# Diagrama_prima_rio.net
KiCad netlist of a schematic drawn in EAGLE
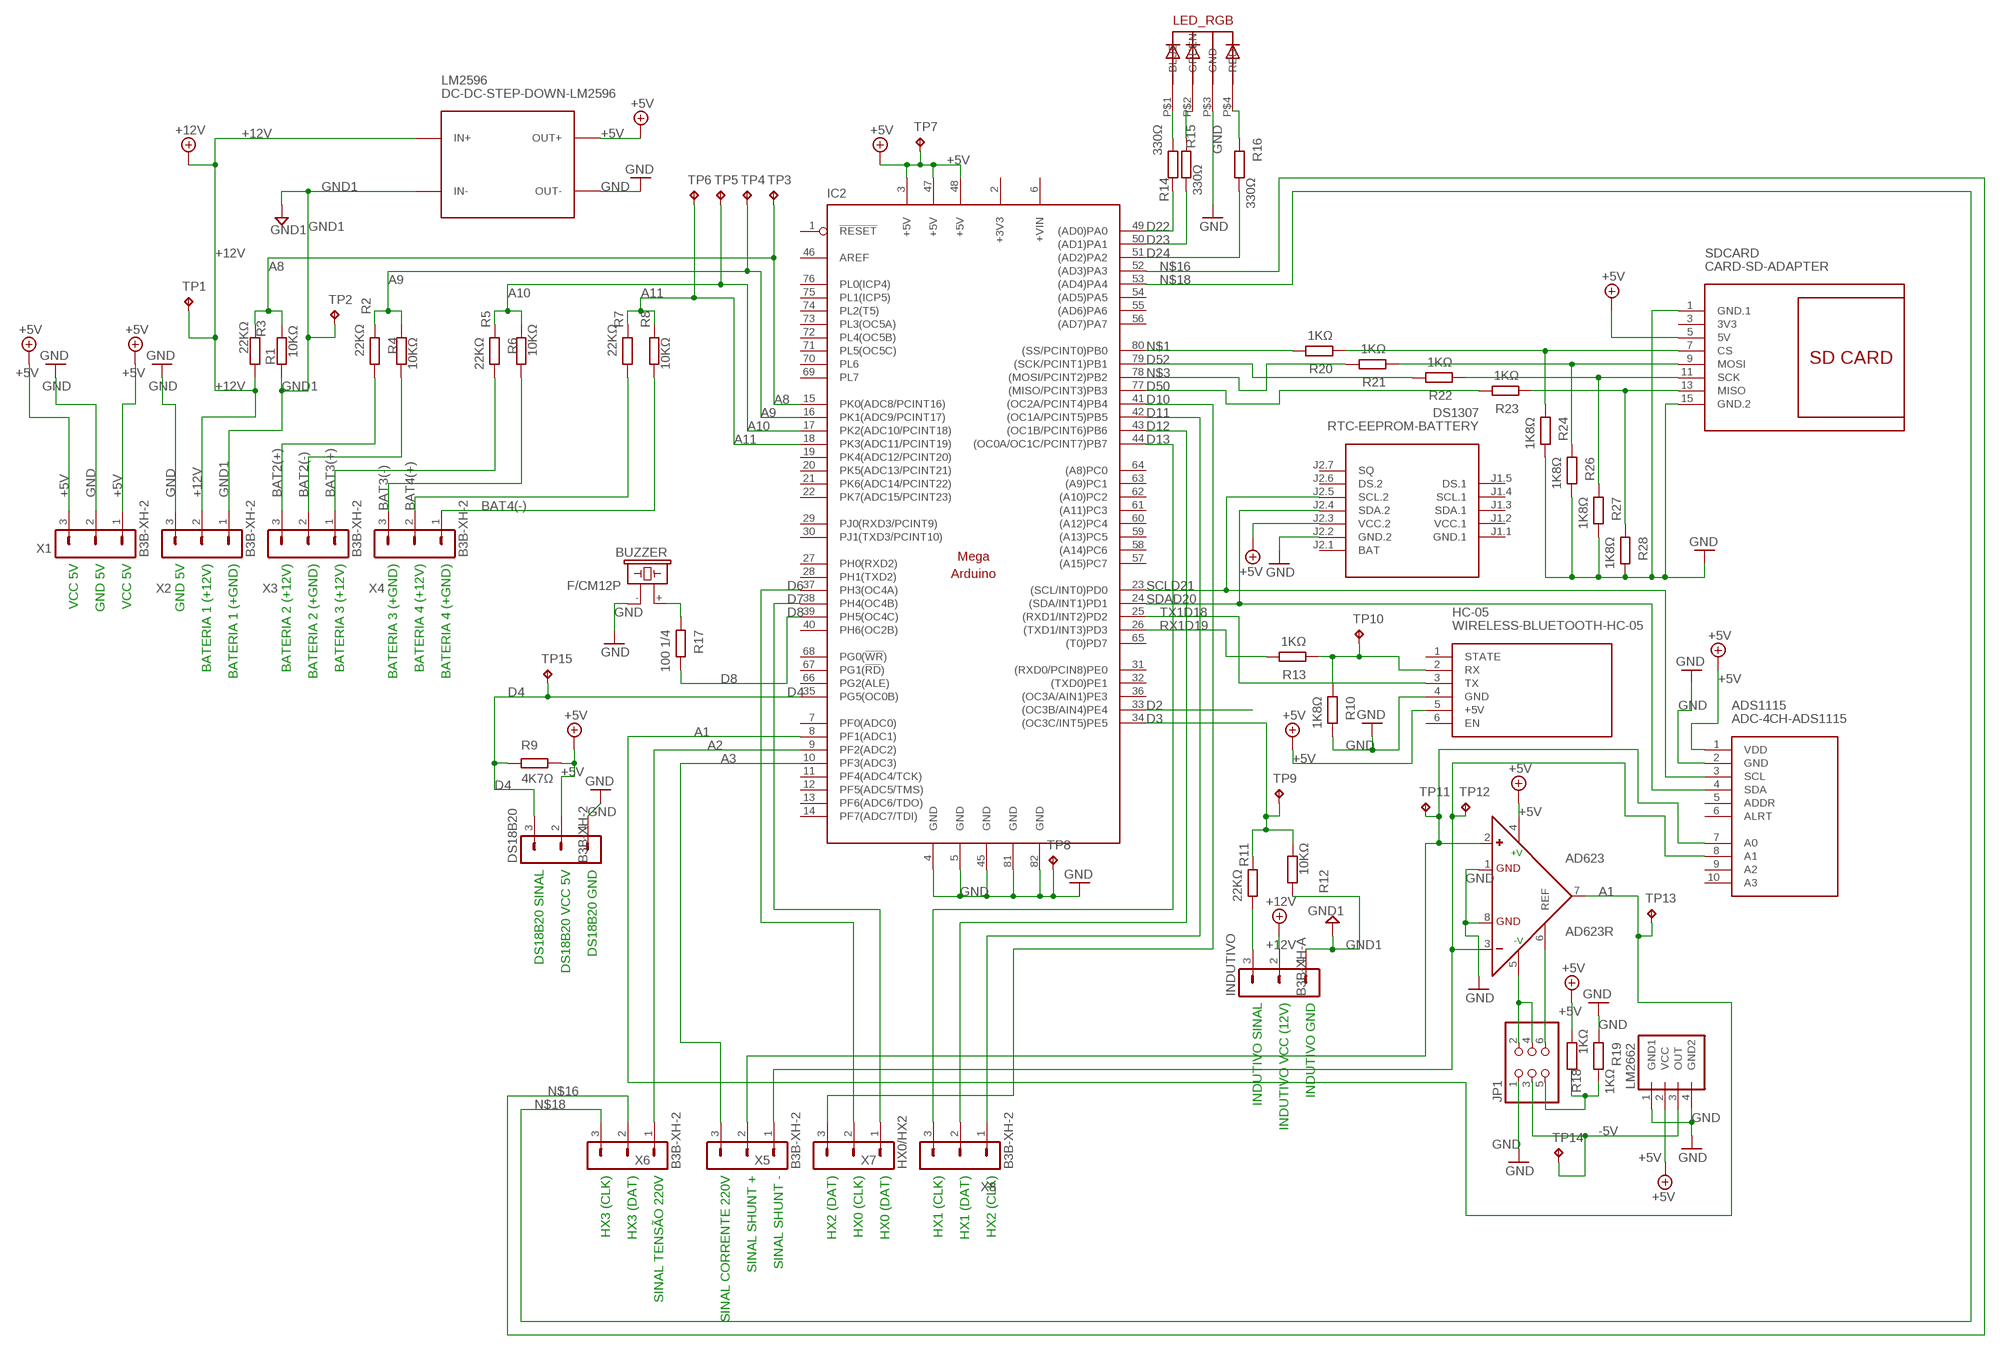
[diagram p0: schematic, sheet 1]

(export (version "E")
  (design (tool "Eeschema 10.0.6"))
  (components
    (comp (ref "AD623")
      (value "AD623R")
      (footprint "eagle-import:SO8")
      (fields (field (name "MPN") "AD623ARZ."))
      (libsource (lib "eagle-import") (part "AD623R"))
    )
    (comp (ref "ADS1115")
      (value "ADC-4CH-ADS1115")
      (footprint "eagle-import:ADC-4CH-ADS1115")
      (libsource (lib "eagle-import") (part "ADC-4CH-ADS1115"))
    )
    (comp (ref "BUZZER")
      (value "F/CM12P")
      (footprint "eagle-import:F_CM12P")
      (libsource (lib "eagle-import") (part "F/CM12P"))
    )
    (comp (ref "DS18B20")
      (value "B3B-XH-2")
      (footprint "eagle-import:B3B-XH-A")
      (libsource (lib "eagle-import") (part "B3B-XH-2"))
    )
    (comp (ref "DS1307")
      (value "RTC-EEPROM-BATTERY")
      (footprint "eagle-import:RTC-EEPROM-BATTERY")
      (libsource (lib "eagle-import") (part "RTC-EEPROM-BATTERY"))
    )
    (comp (ref "HC-05")
      (value "WIRELESS-BLUETOOTH-HC-05")
      (footprint "eagle-import:WIRELESS-BLUETOOTH-HC-05")
      (libsource (lib "eagle-import") (part "WIRELESS-BLUETOOTH-HC-05"))
    )
    (comp (ref "IC2")
      (value "MEGAARDUINO_11")
      (footprint "eagle-import:MEGA_ARDUINO_1")
      (libsource (lib "eagle-import") (part "MEGAARDUINO_11"))
    )
    (comp (ref "INDUTIVO")
      (value "B3B-XH-A")
      (footprint "eagle-import:B3B-XH-A")
      (libsource (lib "eagle-import") (part "con-JST XH_14082343_B3B-XH-A"))
    )
    (comp (ref "JP1")
      (value "PINHD-2X3")
      (footprint "eagle-import:2X03")
      (libsource (lib "eagle-import") (part "PINHD-2X3"))
    )
    (comp (ref "LED_RGB")
      (value "5MMRGBLED")
      (footprint "eagle-import:LED5MMRGB")
      (libsource (lib "eagle-import") (part "5MMRGBLED"))
    )
    (comp (ref "LM2596")
      (value "DC-DC-STEP-DOWN-LM2596")
      (footprint "eagle-import:DC-DC-STEP-DOWN-LM2596")
      (libsource (lib "eagle-import") (part "DC-DC-STEP-DOWN-LM2596"))
    )
    (comp (ref "LM2662")
      (value "LM2662")
      (footprint "eagle-import:LM2662")
      (libsource (lib "eagle-import") (part "LM2662"))
    )
    (comp (ref "R1")
      (value "10KΩ")
      (footprint "eagle-import:1_4W-0.41K")
      (libsource (lib "eagle-import") (part "1K1/4RESISTOR"))
    )
    (comp (ref "R2")
      (value "22KΩ")
      (footprint "eagle-import:1_4W-0.41K")
      (libsource (lib "eagle-import") (part "1K1/4RESISTOR"))
    )
    (comp (ref "R3")
      (value "22KΩ")
      (footprint "eagle-import:1_4W-0.41K")
      (libsource (lib "eagle-import") (part "1K1/4RESISTOR"))
    )
    (comp (ref "R4")
      (value "10KΩ")
      (footprint "eagle-import:1_4W-0.41K")
      (libsource (lib "eagle-import") (part "1K1/4RESISTOR"))
    )
    (comp (ref "R5")
      (value "22KΩ")
      (footprint "eagle-import:1_4W-0.41K")
      (libsource (lib "eagle-import") (part "1K1/4RESISTOR"))
    )
    (comp (ref "R6")
      (value "10KΩ")
      (footprint "eagle-import:1_4W-0.41K")
      (libsource (lib "eagle-import") (part "1K1/4RESISTOR"))
    )
    (comp (ref "R7")
      (value "22KΩ")
      (footprint "eagle-import:1_4W-0.41K")
      (libsource (lib "eagle-import") (part "1K1/4RESISTOR"))
    )
    (comp (ref "R8")
      (value "10KΩ")
      (footprint "eagle-import:1_4W-0.41K")
      (libsource (lib "eagle-import") (part "1K1/4RESISTOR"))
    )
    (comp (ref "R9")
      (value "4K7Ω")
      (footprint "eagle-import:1_4W-0.41K")
      (libsource (lib "eagle-import") (part "1K1/4RESISTOR"))
    )
    (comp (ref "R10")
      (value "1K8Ω")
      (footprint "eagle-import:1_4W-0.41K")
      (libsource (lib "eagle-import") (part "1K1/4RESISTOR"))
    )
    (comp (ref "R11")
      (value "22KΩ")
      (footprint "eagle-import:1_4W-0.41K")
      (libsource (lib "eagle-import") (part "1K1/4RESISTOR"))
    )
    (comp (ref "R12")
      (value "10KΩ")
      (footprint "eagle-import:1_4W-0.41K")
      (libsource (lib "eagle-import") (part "1K1/4RESISTOR"))
    )
    (comp (ref "R13")
      (value "1KΩ")
      (footprint "eagle-import:1_4W-0.41K")
      (libsource (lib "eagle-import") (part "1K1/4RESISTOR"))
    )
    (comp (ref "R14")
      (value "330Ω")
      (footprint "eagle-import:1_4W-0.41K")
      (libsource (lib "eagle-import") (part "1K1/4RESISTOR"))
    )
    (comp (ref "R15")
      (value "330Ω")
      (footprint "eagle-import:1_4W-0.41K")
      (libsource (lib "eagle-import") (part "1K1/4RESISTOR"))
    )
    (comp (ref "R16")
      (value "330Ω")
      (footprint "eagle-import:1_4W-0.41K")
      (libsource (lib "eagle-import") (part "1K1/4RESISTOR"))
    )
    (comp (ref "R17")
      (value "100 1/4")
      (footprint "eagle-import:1_4W-0.41K")
      (libsource (lib "eagle-import") (part "1K1/4RESISTOR"))
    )
    (comp (ref "R18")
      (value "1KΩ")
      (footprint "eagle-import:1_4W-0.41K")
      (libsource (lib "eagle-import") (part "1K1/4RESISTOR"))
    )
    (comp (ref "R19")
      (value "1KΩ")
      (footprint "eagle-import:1_4W-0.41K")
      (libsource (lib "eagle-import") (part "1K1/4RESISTOR"))
    )
    (comp (ref "R20")
      (value "1KΩ")
      (footprint "eagle-import:1_4W-0.41K")
      (libsource (lib "eagle-import") (part "1K1/4RESISTOR"))
    )
    (comp (ref "R21")
      (value "1KΩ")
      (footprint "eagle-import:1_4W-0.41K")
      (libsource (lib "eagle-import") (part "1K1/4RESISTOR"))
    )
    (comp (ref "R22")
      (value "1KΩ")
      (footprint "eagle-import:1_4W-0.41K")
      (libsource (lib "eagle-import") (part "1K1/4RESISTOR"))
    )
    (comp (ref "R23")
      (value "1KΩ")
      (footprint "eagle-import:1_4W-0.41K")
      (libsource (lib "eagle-import") (part "1K1/4RESISTOR"))
    )
    (comp (ref "R24")
      (value "1K8Ω")
      (footprint "eagle-import:1_4W-0.41K")
      (libsource (lib "eagle-import") (part "1K1/4RESISTOR"))
    )
    (comp (ref "R26")
      (value "1K8Ω")
      (footprint "eagle-import:1_4W-0.41K")
      (libsource (lib "eagle-import") (part "1K1/4RESISTOR"))
    )
    (comp (ref "R27")
      (value "1K8Ω")
      (footprint "eagle-import:1_4W-0.41K")
      (libsource (lib "eagle-import") (part "1K1/4RESISTOR"))
    )
    (comp (ref "R28")
      (value "1K8Ω")
      (footprint "eagle-import:1_4W-0.41K")
      (libsource (lib "eagle-import") (part "1K1/4RESISTOR"))
    )
    (comp (ref "SDCARD")
      (value "CARD-SD-ADAPTER")
      (footprint "eagle-import:CARD-SD-ADAPTER")
      (libsource (lib "eagle-import") (part "CARD-SD-ADAPTER"))
    )
    (comp (ref "TP1")
      (value "TPB1,27")
      (footprint "eagle-import:B1,27")
      (libsource (lib "eagle-import") (part "TPB1,27"))
    )
    (comp (ref "TP2")
      (value "TPB1,27")
      (footprint "eagle-import:B1,27")
      (libsource (lib "eagle-import") (part "TPB1,27"))
    )
    (comp (ref "TP3")
      (value "TPB1,27")
      (footprint "eagle-import:B1,27")
      (libsource (lib "eagle-import") (part "TPB1,27"))
    )
    (comp (ref "TP4")
      (value "TPB1,27")
      (footprint "eagle-import:B1,27")
      (libsource (lib "eagle-import") (part "TPB1,27"))
    )
    (comp (ref "TP5")
      (value "TPB1,27")
      (footprint "eagle-import:B1,27")
      (libsource (lib "eagle-import") (part "TPB1,27"))
    )
    (comp (ref "TP6")
      (value "TPB1,27")
      (footprint "eagle-import:B1,27")
      (libsource (lib "eagle-import") (part "TPB1,27"))
    )
    (comp (ref "TP7")
      (value "TPB1,27")
      (footprint "eagle-import:B1,27")
      (libsource (lib "eagle-import") (part "TPB1,27"))
    )
    (comp (ref "TP8")
      (value "TPB1,27")
      (footprint "eagle-import:B1,27")
      (libsource (lib "eagle-import") (part "TPB1,27"))
    )
    (comp (ref "TP9")
      (value "TPB1,27")
      (footprint "eagle-import:B1,27")
      (libsource (lib "eagle-import") (part "TPB1,27"))
    )
    (comp (ref "TP10")
      (value "TPB1,27")
      (footprint "eagle-import:B1,27")
      (libsource (lib "eagle-import") (part "TPB1,27"))
    )
    (comp (ref "TP11")
      (value "TPB1,27")
      (footprint "eagle-import:B1,27")
      (libsource (lib "eagle-import") (part "TPB1,27"))
    )
    (comp (ref "TP12")
      (value "TPB1,27")
      (footprint "eagle-import:B1,27")
      (libsource (lib "eagle-import") (part "TPB1,27"))
    )
    (comp (ref "TP13")
      (value "TPB1,27")
      (footprint "eagle-import:B1,27")
      (libsource (lib "eagle-import") (part "TPB1,27"))
    )
    (comp (ref "TP14")
      (value "TPB1,27")
      (footprint "eagle-import:B1,27")
      (libsource (lib "eagle-import") (part "TPB1,27"))
    )
    (comp (ref "TP15")
      (value "TPB1,27")
      (footprint "eagle-import:B1,27")
      (libsource (lib "eagle-import") (part "TPB1,27"))
    )
    (comp (ref "X1")
      (value "B3B-XH-2")
      (footprint "eagle-import:B3B-XH-A")
      (libsource (lib "eagle-import") (part "con-JST XH_14082343_B3B-XH-2"))
    )
    (comp (ref "X2")
      (value "B3B-XH-2")
      (footprint "eagle-import:B3B-XH-A")
      (libsource (lib "eagle-import") (part "con-JST XH_14082343_B3B-XH-2"))
    )
    (comp (ref "X3")
      (value "B3B-XH-2")
      (footprint "eagle-import:B3B-XH-A")
      (libsource (lib "eagle-import") (part "con-JST XH_14082343_B3B-XH-2"))
    )
    (comp (ref "X4")
      (value "B3B-XH-2")
      (footprint "eagle-import:B3B-XH-A")
      (libsource (lib "eagle-import") (part "con-JST XH_14082343_B3B-XH-2"))
    )
    (comp (ref "X5")
      (value "B3B-XH-2")
      (footprint "eagle-import:B3B-XH-A")
      (libsource (lib "eagle-import") (part "con-JST XH_14082343_B3B-XH-2"))
    )
    (comp (ref "X6")
      (value "B3B-XH-2")
      (footprint "eagle-import:B3B-XH-A")
      (libsource (lib "eagle-import") (part "con-JST XH_14082343_B3B-XH-2"))
    )
    (comp (ref "X7")
      (value "HX0/HX2")
      (footprint "eagle-import:B3B-XH-A")
      (libsource (lib "eagle-import") (part "con-JST XH_14082343_B3B-XH-2"))
    )
    (comp (ref "X8")
      (value "B3B-XH-2")
      (footprint "eagle-import:B3B-XH-A")
      (libsource (lib "eagle-import") (part "con-JST XH_14082343_B3B-XH-2"))
    )
  )
  (nets
    (net (code "1") (name "+5V") (class "Default")
      (node (ref "AD623") (pin "4") (pinfunction "+V_4") (pintype "power_in"))
      (node (ref "ADS1115") (pin "1") (pinfunction "VDD_1") (pintype "power_in"))
      (node (ref "DS1307") (pin "J2.3") (pinfunction "VCC.2_J2.3") (pintype "power_in"))
      (node (ref "DS18B20") (pin "2") (pinfunction "2_2") (pintype "passive"))
      (node (ref "HC-05") (pin "5") (pinfunction "+5V_5") (pintype "power_in"))
      (node (ref "IC2") (pin "3") (pinfunction "+5V_3") (pintype "power_in"))
      (node (ref "IC2") (pin "47") (pinfunction "+5V_47") (pintype "power_in"))
      (node (ref "IC2") (pin "48") (pinfunction "+5V_48") (pintype "power_in"))
      (node (ref "LM2596") (pin "OUT+") (pinfunction "OUT+_OUT+") (pintype "bidirectional"))
      (node (ref "LM2662") (pin "2") (pinfunction "VCC_2") (pintype "bidirectional"))
      (node (ref "R18") (pin "1") (pinfunction "1_1") (pintype "passive"))
      (node (ref "R9") (pin "2") (pinfunction "2_2") (pintype "passive"))
      (node (ref "SDCARD") (pin "5") (pinfunction "5V_5") (pintype "power_in"))
      (node (ref "TP7") (pin "TP") (pinfunction "TP_TP") (pintype "input"))
      (node (ref "X1") (pin "1") (pinfunction "1_1") (pintype "passive"))
      (node (ref "X1") (pin "3") (pinfunction "3_3") (pintype "passive"))
    )
    (net (code "2") (name "+12V") (class "Default")
      (node (ref "INDUTIVO") (pin "2") (pinfunction "2_2") (pintype "passive"))
      (node (ref "LM2596") (pin "IN+") (pinfunction "IN+_IN+") (pintype "bidirectional"))
      (node (ref "R3") (pin "2") (pinfunction "2_2") (pintype "passive"))
      (node (ref "TP1") (pin "TP") (pinfunction "TP_TP") (pintype "input"))
      (node (ref "X2") (pin "2") (pinfunction "2_2") (pintype "passive"))
    )
    (net (code "3") (name "/+3V3") (class "Default")
      (node (ref "IC2") (pin "2") (pinfunction "+3V3_2") (pintype "power_in"))
    )
    (net (code "4") (name "/+VIN") (class "Default")
      (node (ref "IC2") (pin "6") (pinfunction "+VIN_6") (pintype "power_in"))
    )
    (net (code "5") (name "/-5V") (class "Default")
      (node (ref "JP1") (pin "3") (pinfunction "3_3") (pintype "passive"))
      (node (ref "LM2662") (pin "3") (pinfunction "OUT_3") (pintype "bidirectional"))
      (node (ref "TP14") (pin "TP") (pinfunction "TP_TP") (pintype "input"))
    )
    (net (code "6") (name "/3V3") (class "Default")
      (node (ref "SDCARD") (pin "3") (pinfunction "3V3_3") (pintype "power_in"))
    )
    (net (code "7") (name "/A1") (class "Default")
      (node (ref "AD623") (pin "7") (pinfunction "OUT_7") (pintype "output"))
      (node (ref "IC2") (pin "8") (pinfunction "PF1(ADC1)_8") (pintype "bidirectional"))
      (node (ref "TP13") (pin "TP") (pinfunction "TP_TP") (pintype "input"))
    )
    (net (code "8") (name "/A2") (class "Default")
      (node (ref "IC2") (pin "9") (pinfunction "PF2(ADC2)_9") (pintype "bidirectional"))
      (node (ref "X6") (pin "1") (pinfunction "1_1") (pintype "passive"))
    )
    (net (code "9") (name "/A3") (class "Default")
      (node (ref "IC2") (pin "10") (pinfunction "PF3(ADC3)_10") (pintype "bidirectional"))
      (node (ref "X5") (pin "3") (pinfunction "3_3") (pintype "passive"))
    )
    (net (code "10") (name "/A8") (class "Default")
      (node (ref "IC2") (pin "15") (pinfunction "PK0(ADC8/PCINT16)_15") (pintype "bidirectional"))
      (node (ref "R1") (pin "1") (pinfunction "1_1") (pintype "passive"))
      (node (ref "R3") (pin "1") (pinfunction "1_1") (pintype "passive"))
      (node (ref "TP3") (pin "TP") (pinfunction "TP_TP") (pintype "input"))
    )
    (net (code "11") (name "/A9") (class "Default")
      (node (ref "IC2") (pin "16") (pinfunction "PK1(ADC9/PCINT17)_16") (pintype "bidirectional"))
      (node (ref "R2") (pin "1") (pinfunction "1_1") (pintype "passive"))
      (node (ref "R4") (pin "1") (pinfunction "1_1") (pintype "passive"))
      (node (ref "TP4") (pin "TP") (pinfunction "TP_TP") (pintype "input"))
    )
    (net (code "12") (name "/A10") (class "Default")
      (node (ref "IC2") (pin "17") (pinfunction "PK2(ADC10/PCINT18)_17") (pintype "bidirectional"))
      (node (ref "R5") (pin "1") (pinfunction "1_1") (pintype "passive"))
      (node (ref "R6") (pin "1") (pinfunction "1_1") (pintype "passive"))
      (node (ref "TP5") (pin "TP") (pinfunction "TP_TP") (pintype "input"))
    )
    (net (code "13") (name "/A11") (class "Default")
      (node (ref "IC2") (pin "18") (pinfunction "PK3(ADC11/PCINT19)_18") (pintype "bidirectional"))
      (node (ref "R7") (pin "1") (pinfunction "1_1") (pintype "passive"))
      (node (ref "R8") (pin "1") (pinfunction "1_1") (pintype "passive"))
      (node (ref "TP6") (pin "TP") (pinfunction "TP_TP") (pintype "input"))
    )
    (net (code "14") (name "/BAT2(+)") (class "Default")
      (node (ref "R2") (pin "2") (pinfunction "2_2") (pintype "passive"))
      (node (ref "X3") (pin "3") (pinfunction "3_3") (pintype "passive"))
    )
    (net (code "15") (name "/BAT2(-)") (class "Default")
      (node (ref "R4") (pin "2") (pinfunction "2_2") (pintype "passive"))
      (node (ref "X3") (pin "2") (pinfunction "2_2") (pintype "passive"))
    )
    (net (code "16") (name "/BAT3(+)") (class "Default")
      (node (ref "R5") (pin "2") (pinfunction "2_2") (pintype "passive"))
      (node (ref "X3") (pin "1") (pinfunction "1_1") (pintype "passive"))
    )
    (net (code "17") (name "/BAT3(-)") (class "Default")
      (node (ref "R6") (pin "2") (pinfunction "2_2") (pintype "passive"))
      (node (ref "X4") (pin "3") (pinfunction "3_3") (pintype "passive"))
    )
    (net (code "18") (name "/BAT4(+)") (class "Default")
      (node (ref "R7") (pin "2") (pinfunction "2_2") (pintype "passive"))
      (node (ref "X4") (pin "2") (pinfunction "2_2") (pintype "passive"))
    )
    (net (code "19") (name "/BAT4(-)") (class "Default")
      (node (ref "R8") (pin "2") (pinfunction "2_2") (pintype "passive"))
      (node (ref "X4") (pin "1") (pinfunction "1_1") (pintype "passive"))
    )
    (net (code "20") (name "/D2") (class "Default")
      (node (ref "IC2") (pin "33") (pinfunction "(OC3B/AIN4)PE4_33") (pintype "bidirectional"))
    )
    (net (code "21") (name "/D3") (class "Default")
      (node (ref "IC2") (pin "34") (pinfunction "(OC3C/INT5)PE5_34") (pintype "bidirectional"))
      (node (ref "R11") (pin "1") (pinfunction "1_1") (pintype "passive"))
      (node (ref "R12") (pin "1") (pinfunction "1_1") (pintype "passive"))
      (node (ref "TP9") (pin "TP") (pinfunction "TP_TP") (pintype "input"))
    )
    (net (code "22") (name "/D4") (class "Default")
      (node (ref "DS18B20") (pin "3") (pinfunction "3_3") (pintype "passive"))
      (node (ref "IC2") (pin "35") (pinfunction "PG5(OC0B)_35") (pintype "bidirectional"))
      (node (ref "R9") (pin "1") (pinfunction "1_1") (pintype "passive"))
      (node (ref "TP15") (pin "TP") (pinfunction "TP_TP") (pintype "input"))
    )
    (net (code "23") (name "/D6") (class "Default")
      (node (ref "IC2") (pin "37") (pinfunction "PH3(OC4A)_37") (pintype "bidirectional"))
      (node (ref "X7") (pin "2") (pinfunction "2_2") (pintype "passive"))
    )
    (net (code "24") (name "/D7") (class "Default")
      (node (ref "IC2") (pin "38") (pinfunction "PH4(OC4B)_38") (pintype "bidirectional"))
      (node (ref "X7") (pin "1") (pinfunction "1_1") (pintype "passive"))
    )
    (net (code "25") (name "/D8") (class "Default")
      (node (ref "IC2") (pin "39") (pinfunction "PH5(OC4C)_39") (pintype "bidirectional"))
      (node (ref "R17") (pin "2") (pinfunction "2_2") (pintype "passive"))
    )
    (net (code "26") (name "/D10") (class "Default")
      (node (ref "IC2") (pin "41") (pinfunction "(OC2A/PCINT4)PB4_41") (pintype "bidirectional"))
      (node (ref "X7") (pin "3") (pinfunction "3_3") (pintype "passive"))
    )
    (net (code "27") (name "/D11") (class "Default")
      (node (ref "IC2") (pin "42") (pinfunction "(OC1A/PCINT5)PB5_42") (pintype "bidirectional"))
      (node (ref "X8") (pin "1") (pinfunction "1_1") (pintype "passive"))
    )
    (net (code "28") (name "/D12") (class "Default")
      (node (ref "IC2") (pin "43") (pinfunction "(OC1B/PCINT6)PB6_43") (pintype "bidirectional"))
      (node (ref "X8") (pin "2") (pinfunction "2_2") (pintype "passive"))
    )
    (net (code "29") (name "/D13") (class "Default")
      (node (ref "IC2") (pin "44") (pinfunction "(OC0A/OC1C/PCINT7)PB7_44") (pintype "bidirectional"))
      (node (ref "X8") (pin "3") (pinfunction "3_3") (pintype "passive"))
    )
    (net (code "30") (name "/D22") (class "Default")
      (node (ref "IC2") (pin "49") (pinfunction "(AD0)PA0_49") (pintype "bidirectional"))
      (node (ref "R14") (pin "2") (pinfunction "2_2") (pintype "passive"))
    )
    (net (code "31") (name "/D23") (class "Default")
      (node (ref "IC2") (pin "50") (pinfunction "(AD1)PA1_50") (pintype "bidirectional"))
      (node (ref "R15") (pin "2") (pinfunction "2_2") (pintype "passive"))
    )
    (net (code "32") (name "/D24") (class "Default")
      (node (ref "IC2") (pin "51") (pinfunction "(AD2)PA2_51") (pintype "bidirectional"))
      (node (ref "R16") (pin "2") (pinfunction "2_2") (pintype "passive"))
    )
    (net (code "33") (name "/D50") (class "Default")
      (node (ref "IC2") (pin "77") (pinfunction "(MISO/PCINT3)PB3_77") (pintype "bidirectional"))
      (node (ref "R23") (pin "2") (pinfunction "2_2") (pintype "passive"))
    )
    (net (code "34") (name "/D52") (class "Default")
      (node (ref "IC2") (pin "79") (pinfunction "(SCK/PCINT1)PB1_79") (pintype "bidirectional"))
      (node (ref "R22") (pin "2") (pinfunction "2_2") (pintype "passive"))
    )
    (net (code "35") (name "/GND.1") (class "Default")
      (node (ref "DS1307") (pin "J1.1") (pinfunction "GND.1_J1.1") (pintype "power_in"))
    )
    (net (code "36") (name "/N$1") (class "Default")
      (node (ref "IC2") (pin "80") (pinfunction "(SS/PCINT0)PB0_80") (pintype "bidirectional"))
      (node (ref "R20") (pin "2") (pinfunction "2_2") (pintype "passive"))
    )
    (net (code "37") (name "/N$3") (class "Default")
      (node (ref "IC2") (pin "78") (pinfunction "(MOSI/PCINT2)PB2_78") (pintype "bidirectional"))
      (node (ref "R21") (pin "2") (pinfunction "2_2") (pintype "passive"))
    )
    (net (code "38") (name "/N$16") (class "Default")
      (node (ref "IC2") (pin "52") (pinfunction "(AD3)PA3_52") (pintype "bidirectional"))
      (node (ref "X6") (pin "2") (pinfunction "2_2") (pintype "passive"))
    )
    (net (code "39") (name "/N$18") (class "Default")
      (node (ref "IC2") (pin "53") (pinfunction "(AD4)PA4_53") (pintype "bidirectional"))
      (node (ref "X6") (pin "3") (pinfunction "3_3") (pintype "passive"))
    )
    (net (code "40") (name "/RX1D19") (class "Default")
      (node (ref "IC2") (pin "26") (pinfunction "(TXD1/INT3)PD3_26") (pintype "bidirectional"))
      (node (ref "R13") (pin "2") (pinfunction "2_2") (pintype "passive"))
    )
    (net (code "41") (name "/SCLD21") (class "Default")
      (node (ref "ADS1115") (pin "3") (pinfunction "SCL_3") (pintype "bidirectional"))
      (node (ref "DS1307") (pin "J2.5") (pinfunction "SCL.2_J2.5") (pintype "bidirectional"))
      (node (ref "IC2") (pin "23") (pinfunction "(SCL/INT0)PD0_23") (pintype "bidirectional"))
    )
    (net (code "42") (name "/SDAD20") (class "Default")
      (node (ref "ADS1115") (pin "4") (pinfunction "SDA_4") (pintype "bidirectional"))
      (node (ref "DS1307") (pin "J2.4") (pinfunction "SDA.2_J2.4") (pintype "bidirectional"))
      (node (ref "IC2") (pin "24") (pinfunction "(SDA/INT1)PD1_24") (pintype "bidirectional"))
    )
    (net (code "43") (name "/TX1D18") (class "Default")
      (node (ref "HC-05") (pin "3") (pinfunction "TX_3") (pintype "bidirectional"))
      (node (ref "IC2") (pin "25") (pinfunction "(RXD1/INT2)PD2_25") (pintype "bidirectional"))
    )
    (net (code "44") (name "/VCC.1") (class "Default")
      (node (ref "DS1307") (pin "J1.2") (pinfunction "VCC.1_J1.2") (pintype "power_in"))
    )
    (net (code "45") (name "GND") (class "Default")
      (node (ref "AD623") (pin "1") (pinfunction "RG_1") (pintype "passive"))
      (node (ref "AD623") (pin "8") (pinfunction "RG_8") (pintype "passive"))
      (node (ref "ADS1115") (pin "2") (pinfunction "GND_2") (pintype "power_in"))
      (node (ref "BUZZER") (pin "-") (pinfunction "2_-") (pintype "passive"))
      (node (ref "DS1307") (pin "J2.2") (pinfunction "GND.2_J2.2") (pintype "power_in"))
      (node (ref "DS18B20") (pin "1") (pinfunction "1_1") (pintype "passive"))
      (node (ref "HC-05") (pin "4") (pinfunction "GND_4") (pintype "power_in"))
      (node (ref "IC2") (pin "4") (pinfunction "GND_4") (pintype "power_in"))
      (node (ref "IC2") (pin "45") (pinfunction "GND_45") (pintype "power_in"))
      (node (ref "IC2") (pin "5") (pinfunction "GND_5") (pintype "power_in"))
      (node (ref "IC2") (pin "81") (pinfunction "GND_81") (pintype "power_in"))
      (node (ref "IC2") (pin "82") (pinfunction "GND_82") (pintype "power_in"))
      (node (ref "JP1") (pin "1") (pinfunction "1_1") (pintype "passive"))
      (node (ref "LED_RGB") (pin "P$3") (pinfunction "GND_P$3") (pintype "bidirectional"))
      (node (ref "LM2596") (pin "OUT-") (pinfunction "OUT-_OUT-") (pintype "bidirectional"))
      (node (ref "LM2662") (pin "1") (pinfunction "GND1_1") (pintype "bidirectional"))
      (node (ref "LM2662") (pin "4") (pinfunction "GND2_4") (pintype "bidirectional"))
      (node (ref "R10") (pin "2") (pinfunction "2_2") (pintype "passive"))
      (node (ref "R19") (pin "1") (pinfunction "1_1") (pintype "passive"))
      (node (ref "R24") (pin "2") (pinfunction "2_2") (pintype "passive"))
      (node (ref "R26") (pin "2") (pinfunction "2_2") (pintype "passive"))
      (node (ref "R27") (pin "2") (pinfunction "2_2") (pintype "passive"))
      (node (ref "R28") (pin "2") (pinfunction "2_2") (pintype "passive"))
      (node (ref "SDCARD") (pin "1") (pinfunction "GND.1_1") (pintype "power_in"))
      (node (ref "SDCARD") (pin "15") (pinfunction "GND.2_15") (pintype "power_in"))
      (node (ref "TP8") (pin "TP") (pinfunction "TP_TP") (pintype "input"))
      (node (ref "X1") (pin "2") (pinfunction "2_2") (pintype "passive"))
      (node (ref "X2") (pin "3") (pinfunction "3_3") (pintype "passive"))
    )
    (net (code "46") (name "GND1") (class "Default")
      (node (ref "INDUTIVO") (pin "1") (pinfunction "1_1") (pintype "passive"))
      (node (ref "LM2596") (pin "IN-") (pinfunction "IN-_IN-") (pintype "bidirectional"))
      (node (ref "R1") (pin "2") (pinfunction "2_2") (pintype "passive"))
      (node (ref "R12") (pin "2") (pinfunction "2_2") (pintype "passive"))
      (node (ref "TP2") (pin "TP") (pinfunction "TP_TP") (pintype "input"))
      (node (ref "X2") (pin "1") (pinfunction "1_1") (pintype "passive"))
    )
    (net (code "47") (name "Net-(AD623-+)") (class "Default")
      (node (ref "AD623") (pin "2") (pinfunction "+_2") (pintype "input"))
      (node (ref "ADS1115") (pin "7") (pinfunction "A0_7") (pintype "input"))
      (node (ref "TP11") (pin "TP") (pinfunction "TP_TP") (pintype "input"))
      (node (ref "X5") (pin "2") (pinfunction "2_2") (pintype "passive"))
    )
    (net (code "48") (name "Net-(AD623--)") (class "Default")
      (node (ref "AD623") (pin "3") (pinfunction "-_3") (pintype "input"))
      (node (ref "ADS1115") (pin "8") (pinfunction "A1_8") (pintype "input"))
      (node (ref "TP12") (pin "TP") (pinfunction "TP_TP") (pintype "input"))
      (node (ref "X5") (pin "1") (pinfunction "1_1") (pintype "passive"))
    )
    (net (code "49") (name "Net-(AD623--V)") (class "Default")
      (node (ref "AD623") (pin "5") (pinfunction "-V_5") (pintype "power_in"))
      (node (ref "JP1") (pin "2") (pinfunction "2_2") (pintype "passive"))
      (node (ref "JP1") (pin "4") (pinfunction "4_4") (pintype "passive"))
    )
    (net (code "50") (name "Net-(AD623-REF)") (class "Default")
      (node (ref "AD623") (pin "6") (pinfunction "REF_6") (pintype "passive"))
      (node (ref "JP1") (pin "6") (pinfunction "6_6") (pintype "passive"))
    )
    (net (code "51") (name "Net-(BUZZER-1)") (class "Default")
      (node (ref "BUZZER") (pin "+") (pinfunction "1_+") (pintype "passive"))
      (node (ref "R17") (pin "1") (pinfunction "1_1") (pintype "passive"))
    )
    (net (code "52") (name "Net-(HC-05-RX)") (class "Default")
      (node (ref "HC-05") (pin "2") (pinfunction "RX_2") (pintype "bidirectional"))
      (node (ref "R10") (pin "1") (pinfunction "1_1") (pintype "passive"))
      (node (ref "R13") (pin "1") (pinfunction "1_1") (pintype "passive"))
      (node (ref "TP10") (pin "TP") (pinfunction "TP_TP") (pintype "input"))
    )
    (net (code "53") (name "Net-(INDUTIVO-Pad3)") (class "Default")
      (node (ref "INDUTIVO") (pin "3") (pinfunction "3_3") (pintype "passive"))
      (node (ref "R11") (pin "2") (pinfunction "2_2") (pintype "passive"))
    )
    (net (code "54") (name "Net-(JP1-Pad5)") (class "Default")
      (node (ref "JP1") (pin "5") (pinfunction "5_5") (pintype "passive"))
      (node (ref "R18") (pin "2") (pinfunction "2_2") (pintype "passive"))
      (node (ref "R19") (pin "2") (pinfunction "2_2") (pintype "passive"))
    )
    (net (code "55") (name "Net-(LED_RGB-BLUE)") (class "Default")
      (node (ref "LED_RGB") (pin "P$1") (pinfunction "BLUE_P$1") (pintype "bidirectional"))
      (node (ref "R14") (pin "1") (pinfunction "1_1") (pintype "passive"))
    )
    (net (code "56") (name "Net-(LED_RGB-GREEN)") (class "Default")
      (node (ref "LED_RGB") (pin "P$2") (pinfunction "GREEN_P$2") (pintype "bidirectional"))
      (node (ref "R15") (pin "1") (pinfunction "1_1") (pintype "passive"))
    )
    (net (code "57") (name "Net-(LED_RGB-RED)") (class "Default")
      (node (ref "LED_RGB") (pin "P$4") (pinfunction "RED_P$4") (pintype "bidirectional"))
      (node (ref "R16") (pin "1") (pinfunction "1_1") (pintype "passive"))
    )
    (net (code "58") (name "Net-(SDCARD-CS)") (class "Default")
      (node (ref "R20") (pin "1") (pinfunction "1_1") (pintype "passive"))
      (node (ref "R24") (pin "1") (pinfunction "1_1") (pintype "passive"))
      (node (ref "SDCARD") (pin "7") (pinfunction "CS_7") (pintype "bidirectional"))
    )
    (net (code "59") (name "Net-(SDCARD-MISO)") (class "Default")
      (node (ref "R23") (pin "1") (pinfunction "1_1") (pintype "passive"))
      (node (ref "R28") (pin "1") (pinfunction "1_1") (pintype "passive"))
      (node (ref "SDCARD") (pin "13") (pinfunction "MISO_13") (pintype "bidirectional"))
    )
    (net (code "60") (name "Net-(SDCARD-MOSI)") (class "Default")
      (node (ref "R21") (pin "1") (pinfunction "1_1") (pintype "passive"))
      (node (ref "R26") (pin "1") (pinfunction "1_1") (pintype "passive"))
      (node (ref "SDCARD") (pin "9") (pinfunction "MOSI_9") (pintype "bidirectional"))
    )
    (net (code "61") (name "Net-(SDCARD-SCK)") (class "Default")
      (node (ref "R22") (pin "1") (pinfunction "1_1") (pintype "passive"))
      (node (ref "R27") (pin "1") (pinfunction "1_1") (pintype "passive"))
      (node (ref "SDCARD") (pin "11") (pinfunction "SCK_11") (pintype "bidirectional"))
    )
    (net (code "62") (name "unconnected-(ADS1115-A2-Pad9)") (class "Default")
      (node (ref "ADS1115") (pin "9") (pinfunction "A2_9") (pintype "input"))
    )
    (net (code "63") (name "unconnected-(ADS1115-A3-Pad10)") (class "Default")
      (node (ref "ADS1115") (pin "10") (pinfunction "A3_10") (pintype "input"))
    )
    (net (code "64") (name "unconnected-(ADS1115-ADDR-Pad5)") (class "Default")
      (node (ref "ADS1115") (pin "5") (pinfunction "ADDR_5") (pintype "bidirectional"))
    )
    (net (code "65") (name "unconnected-(ADS1115-ALRT-Pad6)") (class "Default")
      (node (ref "ADS1115") (pin "6") (pinfunction "ALRT_6") (pintype "bidirectional"))
    )
    (net (code "66") (name "unconnected-(DS1307-BAT-PadJ2.1)") (class "Default")
      (node (ref "DS1307") (pin "J2.1") (pinfunction "BAT_J2.1") (pintype "bidirectional"))
    )
    (net (code "67") (name "unconnected-(DS1307-DS.1-PadJ1.5)") (class "Default")
      (node (ref "DS1307") (pin "J1.5") (pinfunction "DS.1_J1.5") (pintype "bidirectional"))
    )
    (net (code "68") (name "unconnected-(DS1307-DS.2-PadJ2.6)") (class "Default")
      (node (ref "DS1307") (pin "J2.6") (pinfunction "DS.2_J2.6") (pintype "bidirectional"))
    )
    (net (code "69") (name "unconnected-(DS1307-SCL.1-PadJ1.4)") (class "Default")
      (node (ref "DS1307") (pin "J1.4") (pinfunction "SCL.1_J1.4") (pintype "bidirectional"))
    )
    (net (code "70") (name "unconnected-(DS1307-SDA.1-PadJ1.3)") (class "Default")
      (node (ref "DS1307") (pin "J1.3") (pinfunction "SDA.1_J1.3") (pintype "bidirectional"))
    )
    (net (code "71") (name "unconnected-(DS1307-SQ-PadJ2.7)") (class "Default")
      (node (ref "DS1307") (pin "J2.7") (pinfunction "SQ_J2.7") (pintype "bidirectional"))
    )
    (net (code "72") (name "unconnected-(HC-05-EN-Pad6)") (class "Default")
      (node (ref "HC-05") (pin "6") (pinfunction "EN_6") (pintype "bidirectional"))
    )
    (net (code "73") (name "unconnected-(HC-05-STATE-Pad1)") (class "Default")
      (node (ref "HC-05") (pin "1") (pinfunction "STATE_1") (pintype "bidirectional"))
    )
    (net (code "74") (name "unconnected-(IC2-(A8)PC0-Pad64)") (class "Default")
      (node (ref "IC2") (pin "64") (pinfunction "(A8)PC0_64") (pintype "bidirectional"))
    )
    (net (code "75") (name "unconnected-(IC2-(A9)PC1-Pad63)") (class "Default")
      (node (ref "IC2") (pin "63") (pinfunction "(A9)PC1_63") (pintype "bidirectional"))
    )
    (net (code "76") (name "unconnected-(IC2-(A10)PC2-Pad62)") (class "Default")
      (node (ref "IC2") (pin "62") (pinfunction "(A10)PC2_62") (pintype "bidirectional"))
    )
    (net (code "77") (name "unconnected-(IC2-(A11)PC3-Pad61)") (class "Default")
      (node (ref "IC2") (pin "61") (pinfunction "(A11)PC3_61") (pintype "bidirectional"))
    )
    (net (code "78") (name "unconnected-(IC2-(A12)PC4-Pad60)") (class "Default")
      (node (ref "IC2") (pin "60") (pinfunction "(A12)PC4_60") (pintype "bidirectional"))
    )
    (net (code "79") (name "unconnected-(IC2-(A13)PC5-Pad59)") (class "Default")
      (node (ref "IC2") (pin "59") (pinfunction "(A13)PC5_59") (pintype "bidirectional"))
    )
    (net (code "80") (name "unconnected-(IC2-(A14)PC6-Pad58)") (class "Default")
      (node (ref "IC2") (pin "58") (pinfunction "(A14)PC6_58") (pintype "bidirectional"))
    )
    (net (code "81") (name "unconnected-(IC2-(A15)PC7-Pad57)") (class "Default")
      (node (ref "IC2") (pin "57") (pinfunction "(A15)PC7_57") (pintype "bidirectional"))
    )
    (net (code "82") (name "unconnected-(IC2-(AD5)PA5-Pad54)") (class "Default")
      (node (ref "IC2") (pin "54") (pinfunction "(AD5)PA5_54") (pintype "bidirectional"))
    )
    (net (code "83") (name "unconnected-(IC2-(AD6)PA6-Pad55)") (class "Default")
      (node (ref "IC2") (pin "55") (pinfunction "(AD6)PA6_55") (pintype "bidirectional"))
    )
    (net (code "84") (name "unconnected-(IC2-(AD7)PA7-Pad56)") (class "Default")
      (node (ref "IC2") (pin "56") (pinfunction "(AD7)PA7_56") (pintype "bidirectional"))
    )
    (net (code "85") (name "unconnected-(IC2-(OC3A{slash}AIN1)PE3-Pad36)") (class "Default")
      (node (ref "IC2") (pin "36") (pinfunction "(OC3A/AIN1)PE3_36") (pintype "bidirectional"))
    )
    (net (code "86") (name "unconnected-(IC2-(RXD0{slash}PCIN8)PE0-Pad31)") (class "Default")
      (node (ref "IC2") (pin "31") (pinfunction "(RXD0/PCIN8)PE0_31") (pintype "bidirectional"))
    )
    (net (code "87") (name "unconnected-(IC2-(T0)PD7-Pad65)") (class "Default")
      (node (ref "IC2") (pin "65") (pinfunction "(T0)PD7_65") (pintype "bidirectional"))
    )
    (net (code "88") (name "unconnected-(IC2-(TXD0)PE1-Pad32)") (class "Default")
      (node (ref "IC2") (pin "32") (pinfunction "(TXD0)PE1_32") (pintype "bidirectional"))
    )
    (net (code "89") (name "unconnected-(IC2-AREF-Pad46)") (class "Default")
      (node (ref "IC2") (pin "46") (pinfunction "AREF_46") (pintype "bidirectional"))
    )
    (net (code "90") (name "unconnected-(IC2-PF0(ADC0)-Pad7)") (class "Default")
      (node (ref "IC2") (pin "7") (pinfunction "PF0(ADC0)_7") (pintype "bidirectional"))
    )
    (net (code "91") (name "unconnected-(IC2-PF4(ADC4{slash}TCK)-Pad11)") (class "Default")
      (node (ref "IC2") (pin "11") (pinfunction "PF4(ADC4/TCK)_11") (pintype "bidirectional"))
    )
    (net (code "92") (name "unconnected-(IC2-PF5(ADC5{slash}TMS)-Pad12)") (class "Default")
      (node (ref "IC2") (pin "12") (pinfunction "PF5(ADC5/TMS)_12") (pintype "bidirectional"))
    )
    (net (code "93") (name "unconnected-(IC2-PF6(ADC6{slash}TDO)-Pad13)") (class "Default")
      (node (ref "IC2") (pin "13") (pinfunction "PF6(ADC6/TDO)_13") (pintype "bidirectional"))
    )
    (net (code "94") (name "unconnected-(IC2-PF7(ADC7{slash}TDI)-Pad14)") (class "Default")
      (node (ref "IC2") (pin "14") (pinfunction "PF7(ADC7/TDI)_14") (pintype "bidirectional"))
    )
    (net (code "95") (name "unconnected-(IC2-PG0(~{WR})-Pad68)") (class "Default")
      (node (ref "IC2") (pin "68") (pinfunction "PG0(~{WR})_68") (pintype "bidirectional"))
    )
    (net (code "96") (name "unconnected-(IC2-PG1(~{RD})-Pad67)") (class "Default")
      (node (ref "IC2") (pin "67") (pinfunction "PG1(~{RD})_67") (pintype "bidirectional"))
    )
    (net (code "97") (name "unconnected-(IC2-PG2(ALE)-Pad66)") (class "Default")
      (node (ref "IC2") (pin "66") (pinfunction "PG2(ALE)_66") (pintype "bidirectional"))
    )
    (net (code "98") (name "unconnected-(IC2-PH0(RXD2)-Pad27)") (class "Default")
      (node (ref "IC2") (pin "27") (pinfunction "PH0(RXD2)_27") (pintype "bidirectional"))
    )
    (net (code "99") (name "unconnected-(IC2-PH1(TXD2)-Pad28)") (class "Default")
      (node (ref "IC2") (pin "28") (pinfunction "PH1(TXD2)_28") (pintype "bidirectional"))
    )
    (net (code "100") (name "unconnected-(IC2-PH6(OC2B)-Pad40)") (class "Default")
      (node (ref "IC2") (pin "40") (pinfunction "PH6(OC2B)_40") (pintype "bidirectional"))
    )
    (net (code "101") (name "unconnected-(IC2-PJ0(RXD3{slash}PCINT9)-Pad29)") (class "Default")
      (node (ref "IC2") (pin "29") (pinfunction "PJ0(RXD3/PCINT9)_29") (pintype "bidirectional"))
    )
    (net (code "102") (name "unconnected-(IC2-PJ1(TXD3{slash}PCINT10)-Pad30)") (class "Default")
      (node (ref "IC2") (pin "30") (pinfunction "PJ1(TXD3/PCINT10)_30") (pintype "bidirectional"))
    )
    (net (code "103") (name "unconnected-(IC2-PK4(ADC12{slash}PCINT20)-Pad19)") (class "Default")
      (node (ref "IC2") (pin "19") (pinfunction "PK4(ADC12/PCINT20)_19") (pintype "bidirectional"))
    )
    (net (code "104") (name "unconnected-(IC2-PK5(ADC13{slash}PCINT21)-Pad20)") (class "Default")
      (node (ref "IC2") (pin "20") (pinfunction "PK5(ADC13/PCINT21)_20") (pintype "bidirectional"))
    )
    (net (code "105") (name "unconnected-(IC2-PK6(ADC14{slash}PCINT22)-Pad21)") (class "Default")
      (node (ref "IC2") (pin "21") (pinfunction "PK6(ADC14/PCINT22)_21") (pintype "bidirectional"))
    )
    (net (code "106") (name "unconnected-(IC2-PK7(ADC15{slash}PCINT23)-Pad22)") (class "Default")
      (node (ref "IC2") (pin "22") (pinfunction "PK7(ADC15/PCINT23)_22") (pintype "bidirectional"))
    )
    (net (code "107") (name "unconnected-(IC2-PL0(ICP4)-Pad76)") (class "Default")
      (node (ref "IC2") (pin "76") (pinfunction "PL0(ICP4)_76") (pintype "bidirectional"))
    )
    (net (code "108") (name "unconnected-(IC2-PL1(ICP5)-Pad75)") (class "Default")
      (node (ref "IC2") (pin "75") (pinfunction "PL1(ICP5)_75") (pintype "bidirectional"))
    )
    (net (code "109") (name "unconnected-(IC2-PL2(T5)-Pad74)") (class "Default")
      (node (ref "IC2") (pin "74") (pinfunction "PL2(T5)_74") (pintype "bidirectional"))
    )
    (net (code "110") (name "unconnected-(IC2-PL3(OC5A)-Pad73)") (class "Default")
      (node (ref "IC2") (pin "73") (pinfunction "PL3(OC5A)_73") (pintype "bidirectional"))
    )
    (net (code "111") (name "unconnected-(IC2-PL4(OC5B)-Pad72)") (class "Default")
      (node (ref "IC2") (pin "72") (pinfunction "PL4(OC5B)_72") (pintype "bidirectional"))
    )
    (net (code "112") (name "unconnected-(IC2-PL5(OC5C)-Pad71)") (class "Default")
      (node (ref "IC2") (pin "71") (pinfunction "PL5(OC5C)_71") (pintype "bidirectional"))
    )
    (net (code "113") (name "unconnected-(IC2-PL6-Pad70)") (class "Default")
      (node (ref "IC2") (pin "70") (pinfunction "PL6_70") (pintype "bidirectional"))
    )
    (net (code "114") (name "unconnected-(IC2-PL7-Pad69)") (class "Default")
      (node (ref "IC2") (pin "69") (pinfunction "PL7_69") (pintype "bidirectional"))
    )
    (net (code "115") (name "unconnected-(IC2-~{RESET}-Pad1)") (class "Default")
      (node (ref "IC2") (pin "1") (pinfunction "~{RESET}_1") (pintype "bidirectional"))
    )
  )
)
